# 48V-5V_Buck.net
KiCad netlist of a schematic drawn in Altium Designer
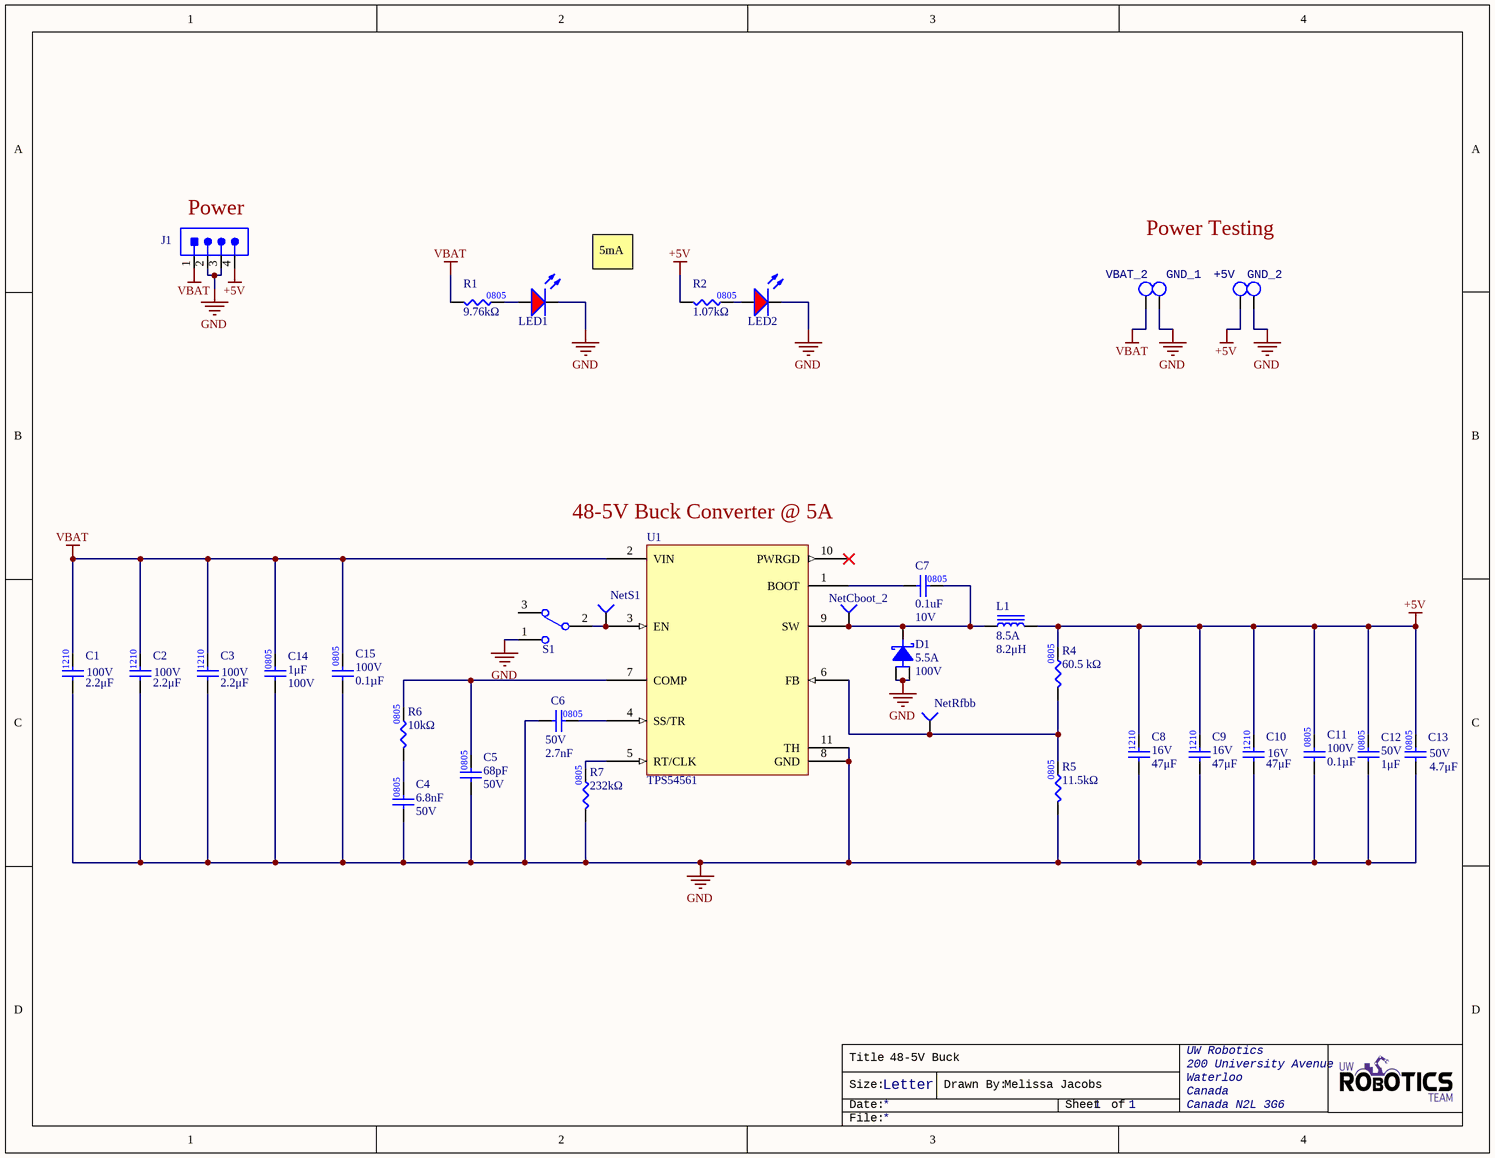
[diagram p0: 48V-5V Buck.SchDoc]

(export (version "E")
  (design (tool "Eeschema 10.0.6"))
  (components
    (comp (ref "+5V")
      (value "TESTPOINT_LOOP")
      (footprint "TESTPOINT_LOOP")
      (description "TESTPOINT THRUHOLE")
      (libsource (lib "UWRT_Schematic_Library_2020") (part "TESTPOINT_LOOP"))
    )
    (comp (ref "C1")
      (value "2.2μF")
      (footprint "CAPC3225X270N")
      (description "CAP CER 2.2UF 100V X7R 1210")
      (fields (field (name "VOLTAGE RATING") "100V") (field (name "Comment") "CAP_2.2uF_100V_1210_1"))
      (libsource (lib "UWRT_Schematic_Library_2020") (part "CAP_2.2uF_100V_1210_1"))
    )
    (comp (ref "C2")
      (value "2.2μF")
      (footprint "CAPC3225X270N")
      (description "CAP CER 2.2UF 100V X7R 1210")
      (fields (field (name "VOLTAGE RATING") "100V") (field (name "Comment") "CAP_2.2uF_100V_1210_1"))
      (libsource (lib "UWRT_Schematic_Library_2020") (part "CAP_2.2uF_100V_1210_1"))
    )
    (comp (ref "C3")
      (value "2.2μF")
      (footprint "CAPC3225X270N")
      (description "CAP CER 2.2UF 100V X7R 1210")
      (fields (field (name "VOLTAGE RATING") "100V") (field (name "Comment") "CAP_2.2uF_100V_1210_1"))
      (libsource (lib "UWRT_Schematic_Library_2020") (part "CAP_2.2uF_100V_1210_1"))
    )
    (comp (ref "C4")
      (value "6.8nF")
      (footprint "CAP0805")
      (description "CAP CER 6800PF 50V C0G/NP0 0805")
      (fields (field (name "VOLTAGE RATING") "50V") (field (name "Comment") "CAP_6.8nF_100V_0805"))
      (libsource (lib "UWRT_Schematic_Library_2020") (part "CAP_6.8nF_100V_0805"))
    )
    (comp (ref "C5")
      (value "68pF")
      (footprint "CAP0805")
      (description "CAP CER 68PF 50V C0G/NP0 0805")
      (fields (field (name "VOLTAGE RATING") "50V") (field (name "Comment") "CAP_68pF_50V_0805"))
      (libsource (lib "UWRT_Schematic_Library_2020") (part "CAP_68pF_50V_0805"))
    )
    (comp (ref "C6")
      (value "2.7nF")
      (footprint "CAP0805")
      (description "CAP CER 2700PF 50V C0G 0805")
      (fields (field (name "VOLTAGE RATING") "50V") (field (name "Comment") "CAP_2.7nF_50V_0805"))
      (libsource (lib "UWRT_Schematic_Library_2020") (part "CAP_2.7nF_50V_0805"))
    )
    (comp (ref "C7")
      (value "0.1uF")
      (footprint "CAP0805")
      (description "CAP CER 0.1uF 10V 0805")
      (fields (field (name "VOLTAGE RATING") "10V") (field (name "Comment") "CAP_0.1uF_10V_0805"))
      (libsource (lib "UWRT_Schematic_Library_2020") (part "CAP_0.1uF_10V_0805"))
    )
    (comp (ref "C8")
      (value "47μF")
      (footprint "CAPC3225X270N")
      (description "CAP CER 47uF 16V X5R 1210")
      (fields (field (name "VOLTAGE RATING") "16V") (field (name "Comment") "CAP_47uF_16V_1210"))
      (libsource (lib "UWRT_Schematic_Library_2020") (part "CAP_47uF_16V_1210"))
    )
    (comp (ref "C9")
      (value "47μF")
      (footprint "CAPC3225X270N")
      (description "CAP CER 47uF 16V X5R 1210")
      (fields (field (name "VOLTAGE RATING") "16V") (field (name "Comment") "CAP_47uF_16V_1210"))
      (libsource (lib "UWRT_Schematic_Library_2020") (part "CAP_47uF_16V_1210"))
    )
    (comp (ref "C10")
      (value "47μF")
      (footprint "CAPC3225X270N")
      (description "CAP CER 47uF 16V X5R 1210")
      (fields (field (name "VOLTAGE RATING") "16V") (field (name "Comment") "CAP_47uF_16V_1210"))
      (libsource (lib "UWRT_Schematic_Library_2020") (part "CAP_47uF_16V_1210"))
    )
    (comp (ref "C11")
      (value "0.1µF")
      (footprint "CAP0805")
      (description "CAP CER 0.1UF 100V X7R 0805")
      (fields (field (name "VOLTAGE RATING") "100V") (field (name "Comment") "CAP_0.1uF_100V_0805"))
      (libsource (lib "UWRT_Schematic_Library_2020") (part "CAP_0.1uF_100V_0805"))
    )
    (comp (ref "C12")
      (value "1μF")
      (footprint "CAP0805")
      (description "CAP CER 1UF 50V X7R 0805")
      (fields
        (field (name "LCSC PART #") "C28323")
        (field (name "VOLTAGE RATING") "50V")
        (field (name "Comment") "CAP_1uF_50V_0805")
      )
      (libsource (lib "UWRT_Schematic_Library_2020") (part "CAP_1uF_50V_0805"))
    )
    (comp (ref "C13")
      (value "4.7μF")
      (footprint "CAP0805")
      (description "CAP CER 4.7UF 50V X5R 0805")
      (fields
        (field (name "LCSC PART #") "C1779")
        (field (name "VOLTAGE RATING") "50V")
        (field (name "Comment") "CAP_4.7uF_50V_0805")
      )
      (libsource (lib "UWRT_Schematic_Library_2020") (part "CAP_4.7uF_50V_0805"))
    )
    (comp (ref "C14")
      (value "1μF")
      (footprint "CAP0805")
      (description "CAP CER 1UF 100V X7S 0805")
      (fields (field (name "VOLTAGE RATING") "100V") (field (name "Comment") "CAP_1uF_100V_0805"))
      (libsource (lib "UWRT_Schematic_Library_2020") (part "CAP_1uF_100V_0805"))
    )
    (comp (ref "C15")
      (value "0.1µF")
      (footprint "CAP0805")
      (description "CAP CER 0.1UF 100V X7R 0805")
      (fields (field (name "VOLTAGE RATING") "100V") (field (name "Comment") "CAP_0.1uF_100V_0805"))
      (libsource (lib "UWRT_Schematic_Library_2020") (part "CAP_0.1uF_100V_0805"))
    )
    (comp (ref "D1")
      (value "5.5A")
      (footprint "D-PAK")
      (description "DIODE SCHOTTKY 100V 5.5A DPAK")
      (fields (field (name "VR (MAX)") "100V"))
      (libsource (lib "UWRT_Schematic_Library_2020") (part "DIO_SCHOTTKY_100V_5.5A"))
    )
    (comp (ref "GND_1")
      (value "TESTPOINT_LOOP")
      (footprint "TESTPOINT_LOOP")
      (description "TESTPOINT THRUHOLE")
      (libsource (lib "UWRT_Schematic_Library_2020") (part "TESTPOINT_LOOP"))
    )
    (comp (ref "GND_2")
      (value "TESTPOINT_LOOP")
      (footprint "TESTPOINT_LOOP")
      (description "TESTPOINT THRUHOLE")
      (libsource (lib "UWRT_Schematic_Library_2020") (part "TESTPOINT_LOOP"))
    )
    (comp (ref "J1")
      (value "CON_2POS_SCREW_TERM")
      (footprint "MPT-04-01-01-L-RA-SD")
      (description "CONN HDR 4POS 5MM R/A SLDR")
      (libsource (lib "UWRT_Schematic_Library_2020") (part "CON_4POS_POWERBLADE_MALE"))
    )
    (comp (ref "L1")
      (value "8.2μH")
      (footprint "IND_8.2uH_8.5A")
      (description "FIXED IND 8.2UH 8.5A 28 MOHM SMD")
      (fields (field (name "CURRENT RATING") "8.5A") (field (name "Comment") "IND_8.2uH_8.5A"))
      (libsource (lib "UWRT_Schematic_Library_2020") (part "IND_8.2uH_8.5A"))
    )
    (comp (ref "LED1")
      (value "LED_RED")
      (footprint "LED_0805_RED")
      (description "LED RED DIFFUSED 0805 SMD")
      (libsource (lib "UWRT_Schematic_Library_2020") (part "LED_RED"))
    )
    (comp (ref "LED2")
      (value "LED_RED")
      (footprint "LED_0805_RED")
      (description "LED RED DIFFUSED 0805 SMD")
      (libsource (lib "UWRT_Schematic_Library_2020") (part "LED_RED"))
    )
    (comp (ref "NetCboot_2")
      (value "TESTPOINT_1MM_CIRCLE")
      (footprint "TESTPOINT_CIRCLE_1MM")
      (description "TESTPOINT 1MM CIRCLE")
      (libsource (lib "UWRT_Schematic_Library_2020") (part "TESTPOINT_1MM_CIRCLE"))
    )
    (comp (ref "NetRfbb")
      (value "TESTPOINT_1MM_CIRCLE")
      (footprint "TESTPOINT_CIRCLE_1MM")
      (description "TESTPOINT 1MM CIRCLE")
      (libsource (lib "UWRT_Schematic_Library_2020") (part "TESTPOINT_1MM_CIRCLE"))
    )
    (comp (ref "NetS1")
      (value "TESTPOINT_1MM_CIRCLE")
      (footprint "TESTPOINT_CIRCLE_1MM")
      (description "TESTPOINT 1MM CIRCLE")
      (libsource (lib "UWRT_Schematic_Library_2020") (part "TESTPOINT_1MM_CIRCLE"))
    )
    (comp (ref "R1")
      (value "9.76kΩ")
      (footprint "RES0805")
      (description "RES 9.76K OHM 1% 1/8W 0805")
      (fields (field (name "Comment") "RES_9.76kΩ_0805_1%"))
      (libsource (lib "UWRT_Schematic_Library_2020") (part "RES_9.76kΩ_0805_1%"))
    )
    (comp (ref "R2")
      (value "1.07kΩ")
      (footprint "RES0805")
      (description "RES 1K OHM 1% 1/8W 0805")
      (fields (field (name "Comment") "RES_1kΩ_0805_1%"))
      (libsource (lib "UWRT_Schematic_Library_2020") (part "RES_1kΩ_0805_1%"))
    )
    (comp (ref "R4")
      (value "60.5 kΩ")
      (footprint "RES0805")
      (description "RES 60.5 kOHM 63 mW 0805")
      (fields (field (name "Comment") "RES_60.4kΩ_0805_1%"))
      (libsource (lib "UWRT_Schematic_Library_2020") (part "RES_60.4kΩ_0805_1%"))
    )
    (comp (ref "R5")
      (value "11.5kΩ")
      (footprint "RES0805")
      (description "RES 11.5K OHM 0.1% 1/10W 0805")
      (fields (field (name "Comment") "RES_11.5kΩ_0805_0.1%"))
      (libsource (lib "UWRT_Schematic_Library_2020") (part "RES_11.5kΩ_0805_0.1%"))
    )
    (comp (ref "R6")
      (value "10kΩ")
      (footprint "RES0805")
      (description "RES 10K OHM 5% 1/8W 0805")
      (fields (field (name "LCSC PART #") "C17414") (field (name "Comment") "RES_10kΩ_0805_5%"))
      (libsource (lib "UWRT_Schematic_Library_2020") (part "RES_10kΩ_0805_5%"))
    )
    (comp (ref "R7")
      (value "232kΩ")
      (footprint "RES0805")
      (description "RES 232K OHM 1% 1/8W 0805")
      (fields (field (name "LCSC PART #") "0") (field (name "Comment") "RES_232kΩ_0805_1%"))
      (libsource (lib "UWRT_Schematic_Library_2020") (part "RES_232kΩ_0805_1%"))
    )
    (comp (ref "S1")
      (value "SW_SLIDE_TOGGLE")
      (footprint "UWRT_Footprint_Library_2020:SW_SLIDE_TOGGLE")
      (description "SWITCH SLIDE SPDT 200MA 30V")
      (libsource (lib "UWRT_Schematic_Library_2020") (part "SW_SLIDE_TOGGLE"))
    )
    (comp (ref "U1")
      (value "TPS54561")
      (footprint "BUCK_TPS54561DPRR")
      (description "Buck Switching Regulator IC Positive Adjustable 0.8V 1 Output 5A 10-WDFN Exposed Pad")
      (libsource (lib "UWRT_Schematic_Library_2020") (part "TPS54561"))
    )
    (comp (ref "VBAT_2")
      (value "TESTPOINT_LOOP")
      (footprint "TESTPOINT_LOOP")
      (description "TESTPOINT THRUHOLE")
      (libsource (lib "UWRT_Schematic_Library_2020") (part "TESTPOINT_LOOP"))
    )
  )
  (nets
    (net (code "1") (name "+5V") (class "Default")
      (node (ref "+5V") (pin "1") (pintype "passive"))
      (node (ref "C10") (pin "2") (pinfunction "2_2") (pintype "passive"))
      (node (ref "C11") (pin "2") (pinfunction "2_2") (pintype "passive"))
      (node (ref "C12") (pin "2") (pinfunction "2_2") (pintype "passive"))
      (node (ref "C13") (pin "2") (pinfunction "2_2") (pintype "passive"))
      (node (ref "C8") (pin "2") (pinfunction "2_2") (pintype "passive"))
      (node (ref "C9") (pin "2") (pinfunction "2_2") (pintype "passive"))
      (node (ref "J1") (pin "4") (pinfunction "2_4") (pintype "passive"))
      (node (ref "L1") (pin "2") (pinfunction "2_2") (pintype "passive"))
      (node (ref "R2") (pin "1") (pinfunction "1_1") (pintype "passive"))
      (node (ref "R4") (pin "2") (pinfunction "2_2") (pintype "passive"))
    )
    (net (code "2") (name "GND") (class "Default")
      (node (ref "C1") (pin "1") (pinfunction "1_1") (pintype "passive"))
      (node (ref "C10") (pin "1") (pinfunction "1_1") (pintype "passive"))
      (node (ref "C11") (pin "1") (pinfunction "1_1") (pintype "passive"))
      (node (ref "C12") (pin "1") (pinfunction "1_1") (pintype "passive"))
      (node (ref "C13") (pin "1") (pinfunction "1_1") (pintype "passive"))
      (node (ref "C14") (pin "1") (pinfunction "1_1") (pintype "passive"))
      (node (ref "C15") (pin "1") (pinfunction "1_1") (pintype "passive"))
      (node (ref "C2") (pin "1") (pinfunction "1_1") (pintype "passive"))
      (node (ref "C3") (pin "1") (pinfunction "1_1") (pintype "passive"))
      (node (ref "C4") (pin "1") (pinfunction "1_1") (pintype "passive"))
      (node (ref "C5") (pin "1") (pinfunction "1_1") (pintype "passive"))
      (node (ref "C6") (pin "1") (pinfunction "1_1") (pintype "passive"))
      (node (ref "C8") (pin "1") (pinfunction "1_1") (pintype "passive"))
      (node (ref "C9") (pin "1") (pinfunction "1_1") (pintype "passive"))
      (node (ref "D1") (pin "1") (pinfunction "Anode_1") (pintype "passive"))
      (node (ref "D1") (pin "3") (pintype "passive"))
      (node (ref "GND_1") (pin "1") (pintype "passive"))
      (node (ref "GND_2") (pin "1") (pintype "passive"))
      (node (ref "J1") (pin "2") (pinfunction "2_2") (pintype "passive"))
      (node (ref "J1") (pin "3") (pinfunction "1_3") (pintype "passive"))
      (node (ref "LED1") (pin "2") (pinfunction "K_2") (pintype "passive"))
      (node (ref "LED2") (pin "2") (pinfunction "K_2") (pintype "passive"))
      (node (ref "R5") (pin "1") (pinfunction "1_1") (pintype "passive"))
      (node (ref "R7") (pin "1") (pinfunction "1_1") (pintype "passive"))
      (node (ref "S1") (pin "1") (pinfunction "1_1") (pintype "passive"))
      (node (ref "U1") (pin "11") (pinfunction "TH_11") (pintype "power_in"))
      (node (ref "U1") (pin "8") (pinfunction "GND_8") (pintype "power_in"))
    )
    (net (code "3") (name "Net-(C4-Pad2)") (class "Default")
      (node (ref "C4") (pin "2") (pinfunction "2_2") (pintype "passive"))
      (node (ref "R6") (pin "1") (pinfunction "1_1") (pintype "passive"))
    )
    (net (code "4") (name "Net-(D1-Cathode)") (class "Default")
      (node (ref "C7") (pin "2") (pinfunction "2_2") (pintype "passive"))
      (node (ref "D1") (pin "2") (pinfunction "Cathode_2") (pintype "passive"))
      (node (ref "L1") (pin "1") (pinfunction "1_1") (pintype "passive"))
      (node (ref "NetCboot_2") (pin "1") (pinfunction "=value_1") (pintype "passive"))
      (node (ref "U1") (pin "9") (pinfunction "SW_9") (pintype "power_in"))
    )
    (net (code "5") (name "Net-(LED1-A)") (class "Default")
      (node (ref "LED1") (pin "1") (pinfunction "A_1") (pintype "passive"))
      (node (ref "R1") (pin "2") (pinfunction "2_2") (pintype "passive"))
    )
    (net (code "6") (name "Net-(LED2-A)") (class "Default")
      (node (ref "LED2") (pin "1") (pinfunction "A_1") (pintype "passive"))
      (node (ref "R2") (pin "2") (pinfunction "2_2") (pintype "passive"))
    )
    (net (code "7") (name "Net-(NetRfbb-=value)") (class "Default")
      (node (ref "NetRfbb") (pin "1") (pinfunction "=value_1") (pintype "passive"))
      (node (ref "R4") (pin "1") (pinfunction "1_1") (pintype "passive"))
      (node (ref "R5") (pin "2") (pinfunction "2_2") (pintype "passive"))
      (node (ref "U1") (pin "6") (pinfunction "FB_6") (pintype "input"))
    )
    (net (code "8") (name "Net-(NetS1-=value)") (class "Default")
      (node (ref "NetS1") (pin "1") (pinfunction "=value_1") (pintype "passive"))
      (node (ref "S1") (pin "2") (pinfunction "2_2") (pintype "passive"))
      (node (ref "U1") (pin "3") (pinfunction "EN_3") (pintype "input"))
    )
    (net (code "9") (name "Net-(U1-BOOT)") (class "Default")
      (node (ref "C7") (pin "1") (pinfunction "1_1") (pintype "passive"))
      (node (ref "U1") (pin "1") (pinfunction "BOOT_1") (pintype "power_in"))
    )
    (net (code "10") (name "Net-(U1-COMP)") (class "Default")
      (node (ref "C5") (pin "2") (pinfunction "2_2") (pintype "passive"))
      (node (ref "R6") (pin "2") (pinfunction "2_2") (pintype "passive"))
      (node (ref "U1") (pin "7") (pinfunction "COMP_7") (pintype "power_in"))
    )
    (net (code "11") (name "Net-(U1-RT{slash}CLK)") (class "Default")
      (node (ref "R7") (pin "2") (pinfunction "2_2") (pintype "passive"))
      (node (ref "U1") (pin "5") (pinfunction "RT/CLK_5") (pintype "input"))
    )
    (net (code "12") (name "Net-(U1-SS{slash}TR)") (class "Default")
      (node (ref "C6") (pin "2") (pinfunction "2_2") (pintype "passive"))
      (node (ref "U1") (pin "4") (pinfunction "SS/TR_4") (pintype "input"))
    )
    (net (code "13") (name "VBAT") (class "Default")
      (node (ref "C1") (pin "2") (pinfunction "2_2") (pintype "passive"))
      (node (ref "C14") (pin "2") (pinfunction "2_2") (pintype "passive"))
      (node (ref "C15") (pin "2") (pinfunction "2_2") (pintype "passive"))
      (node (ref "C2") (pin "2") (pinfunction "2_2") (pintype "passive"))
      (node (ref "C3") (pin "2") (pinfunction "2_2") (pintype "passive"))
      (node (ref "J1") (pin "1") (pinfunction "1_1") (pintype "passive"))
      (node (ref "R1") (pin "1") (pinfunction "1_1") (pintype "passive"))
      (node (ref "U1") (pin "2") (pinfunction "VIN_2") (pintype "power_in"))
      (node (ref "VBAT_2") (pin "1") (pintype "passive"))
    )
    (net (code "14") (name "unconnected-(S1-Pad3)") (class "Default")
      (node (ref "S1") (pin "3") (pinfunction "3_3") (pintype "passive"))
    )
    (net (code "15") (name "unconnected-(U1-PWRGD-Pad10)") (class "Default")
      (node (ref "U1") (pin "10") (pinfunction "PWRGD_10") (pintype "output+no_connect"))
    )
  )
)
